# rc2014_16550.net
KiCad netlist of a schematic drawn in EAGLE
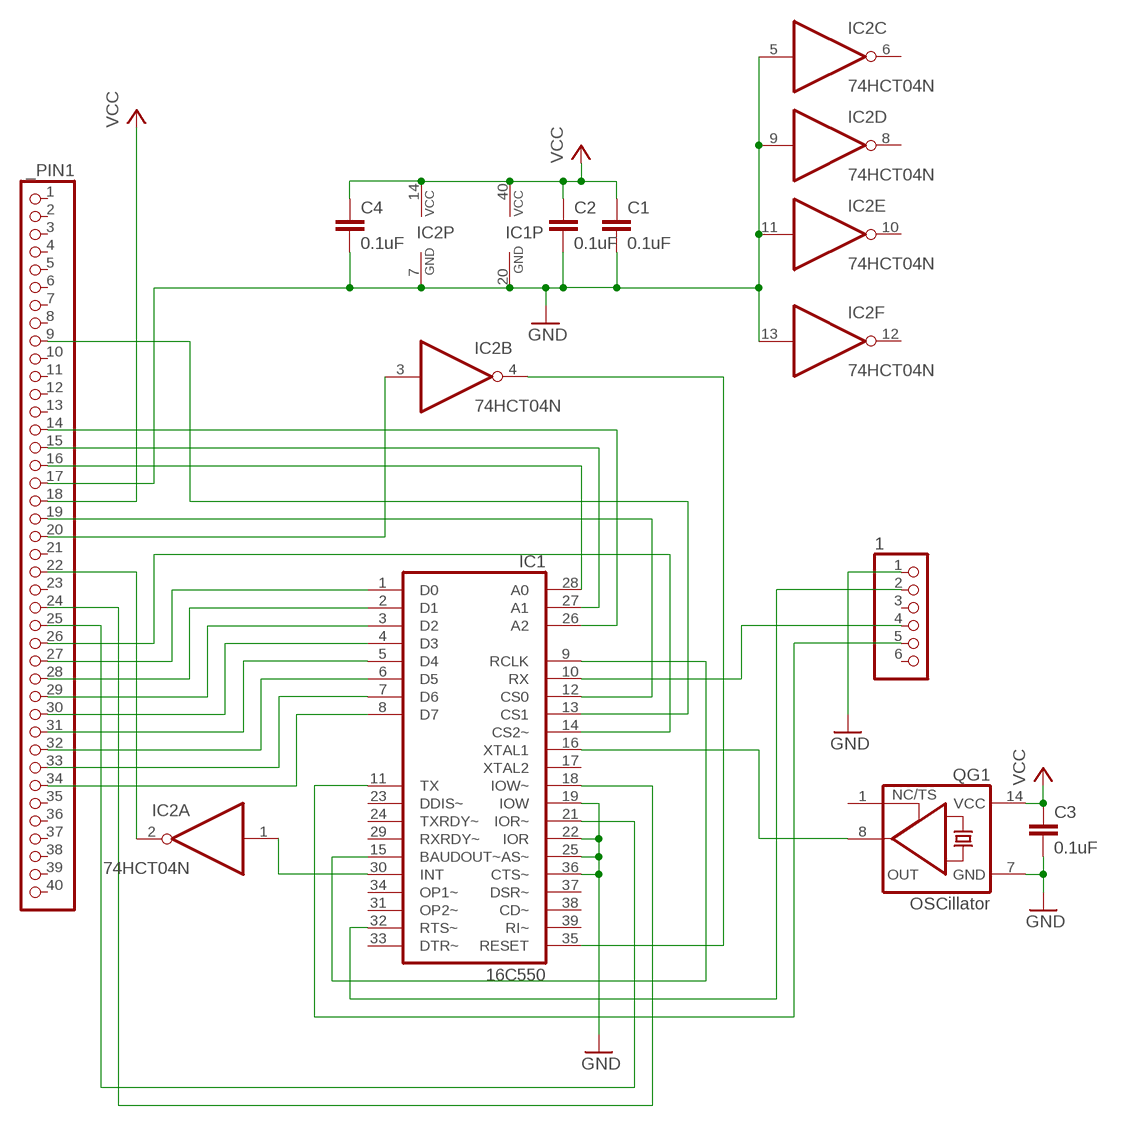
[diagram p0: schematic, sheet 1]

(export (version "E")
  (design (tool "Eeschema 10.0.6"))
  (components
    (comp (ref "1")
      (value "PINHD-1X6")
      (footprint "eagle-import:1X06")
      (libsource (lib "eagle-import") (part "PINHD-1X6"))
    )
    (comp (ref "C1")
      (value "0.1uF")
      (footprint "eagle-import:C050-024X044")
      (libsource (lib "eagle-import") (part "C-EU050-024X044"))
    )
    (comp (ref "C2")
      (value "0.1uF")
      (footprint "eagle-import:C050-024X044")
      (libsource (lib "eagle-import") (part "C-EU050-024X044"))
    )
    (comp (ref "C3")
      (value "0.1uF")
      (footprint "eagle-import:C050-024X044")
      (libsource (lib "eagle-import") (part "C-EU050-024X044"))
    )
    (comp (ref "C4")
      (value "0.1uF")
      (footprint "eagle-import:C050-024X044")
      (libsource (lib "eagle-import") (part "C-EU050-024X044"))
    )
    (comp (ref "IC1")
      (value "16C550")
      (footprint "eagle-import:DIL40")
      (fields (field (name "MPN") "ST16C450CP40"))
      (libsource (lib "eagle-import") (part "XR-16C550P"))
    )
    (comp (ref "IC2")
      (value "74HCT04N")
      (footprint "eagle-import:DIL14")
      (libsource (lib "eagle-import") (part "7404NHCT"))
    )
    (comp (ref "QG1")
      (value "OSCillator")
      (footprint "eagle-import:DIL14S")
      (libsource (lib "eagle-import") (part "XO-14"))
    )
    (comp (ref "_PIN1")
      (value "PINHD-1X40")
      (footprint "eagle-import:1X40")
      (libsource (lib "eagle-import") (part "PINHD-1X40"))
    )
  )
  (nets
    (net (code "1") (name "GND") (class "Default")
      (node (ref "1") (pin "1") (pinfunction "1_1") (pintype "passive"))
      (node (ref "C1") (pin "2") (pinfunction "2_2") (pintype "passive"))
      (node (ref "C2") (pin "2") (pinfunction "2_2") (pintype "passive"))
      (node (ref "C3") (pin "2") (pinfunction "2_2") (pintype "passive"))
      (node (ref "C4") (pin "2") (pinfunction "2_2") (pintype "passive"))
      (node (ref "IC1") (pin "19") (pinfunction "IOW_19") (pintype "input"))
      (node (ref "IC1") (pin "20") (pinfunction "GND_20") (pintype "power_in"))
      (node (ref "IC1") (pin "22") (pinfunction "IOR_22") (pintype "input"))
      (node (ref "IC1") (pin "25") (pinfunction "AS~{}_25") (pintype "input"))
      (node (ref "IC1") (pin "36") (pinfunction "CTS~{}_36") (pintype "input"))
      (node (ref "IC2") (pin "11") (pinfunction "I_11") (pintype "input"))
      (node (ref "IC2") (pin "13") (pinfunction "I_13") (pintype "input"))
      (node (ref "IC2") (pin "5") (pinfunction "I_5") (pintype "input"))
      (node (ref "IC2") (pin "7") (pinfunction "GND_7") (pintype "power_in"))
      (node (ref "IC2") (pin "9") (pinfunction "I_9") (pintype "input"))
      (node (ref "QG1") (pin "7") (pinfunction "GND_7") (pintype "power_in"))
      (node (ref "_PIN1") (pin "17") (pinfunction "17_17") (pintype "passive"))
    )
    (net (code "2") (name "Net-(IC1A-A0)") (class "Default")
      (node (ref "IC1") (pin "28") (pinfunction "A0_28") (pintype "input"))
      (node (ref "_PIN1") (pin "16") (pinfunction "16_16") (pintype "passive"))
    )
    (net (code "3") (name "Net-(IC1A-A1)") (class "Default")
      (node (ref "IC1") (pin "27") (pinfunction "A1_27") (pintype "input"))
      (node (ref "_PIN1") (pin "15") (pinfunction "15_15") (pintype "passive"))
    )
    (net (code "4") (name "Net-(IC1A-A2)") (class "Default")
      (node (ref "IC1") (pin "26") (pinfunction "A2_26") (pintype "input"))
      (node (ref "_PIN1") (pin "14") (pinfunction "14_14") (pintype "passive"))
    )
    (net (code "5") (name "Net-(IC1A-BAUDOUT~{})") (class "Default")
      (node (ref "IC1") (pin "15") (pinfunction "BAUDOUT~{}_15") (pintype "output"))
      (node (ref "IC1") (pin "9") (pinfunction "RCLK_9") (pintype "input"))
    )
    (net (code "6") (name "Net-(IC1A-CS0)") (class "Default")
      (node (ref "IC1") (pin "12") (pinfunction "CS0_12") (pintype "input"))
      (node (ref "_PIN1") (pin "19") (pinfunction "19_19") (pintype "passive"))
    )
    (net (code "7") (name "Net-(IC1A-CS1)") (class "Default")
      (node (ref "IC1") (pin "13") (pinfunction "CS1_13") (pintype "input"))
      (node (ref "_PIN1") (pin "9") (pinfunction "9_9") (pintype "passive"))
    )
    (net (code "8") (name "Net-(IC1A-CS2~{})") (class "Default")
      (node (ref "IC1") (pin "14") (pinfunction "CS2~{}_14") (pintype "input"))
      (node (ref "_PIN1") (pin "26") (pinfunction "26_26") (pintype "passive"))
    )
    (net (code "9") (name "Net-(IC1A-D0)") (class "Default")
      (node (ref "IC1") (pin "1") (pinfunction "D0_1") (pintype "bidirectional"))
      (node (ref "_PIN1") (pin "27") (pinfunction "27_27") (pintype "passive"))
    )
    (net (code "10") (name "Net-(IC1A-D1)") (class "Default")
      (node (ref "IC1") (pin "2") (pinfunction "D1_2") (pintype "bidirectional"))
      (node (ref "_PIN1") (pin "28") (pinfunction "28_28") (pintype "passive"))
    )
    (net (code "11") (name "Net-(IC1A-D2)") (class "Default")
      (node (ref "IC1") (pin "3") (pinfunction "D2_3") (pintype "bidirectional"))
      (node (ref "_PIN1") (pin "29") (pinfunction "29_29") (pintype "passive"))
    )
    (net (code "12") (name "Net-(IC1A-D3)") (class "Default")
      (node (ref "IC1") (pin "4") (pinfunction "D3_4") (pintype "bidirectional"))
      (node (ref "_PIN1") (pin "30") (pinfunction "30_30") (pintype "passive"))
    )
    (net (code "13") (name "Net-(IC1A-D4)") (class "Default")
      (node (ref "IC1") (pin "5") (pinfunction "D4_5") (pintype "bidirectional"))
      (node (ref "_PIN1") (pin "31") (pinfunction "31_31") (pintype "passive"))
    )
    (net (code "14") (name "Net-(IC1A-D5)") (class "Default")
      (node (ref "IC1") (pin "6") (pinfunction "D5_6") (pintype "bidirectional"))
      (node (ref "_PIN1") (pin "32") (pinfunction "32_32") (pintype "passive"))
    )
    (net (code "15") (name "Net-(IC1A-D6)") (class "Default")
      (node (ref "IC1") (pin "7") (pinfunction "D6_7") (pintype "bidirectional"))
      (node (ref "_PIN1") (pin "33") (pinfunction "33_33") (pintype "passive"))
    )
    (net (code "16") (name "Net-(IC1A-D7)") (class "Default")
      (node (ref "IC1") (pin "8") (pinfunction "D7_8") (pintype "bidirectional"))
      (node (ref "_PIN1") (pin "34") (pinfunction "34_34") (pintype "passive"))
    )
    (net (code "17") (name "Net-(IC1A-INT)") (class "Default")
      (node (ref "IC1") (pin "30") (pinfunction "INT_30") (pintype "output"))
      (node (ref "IC2") (pin "1") (pinfunction "I_1") (pintype "input"))
    )
    (net (code "18") (name "Net-(IC1A-IOR~{})") (class "Default")
      (node (ref "IC1") (pin "21") (pinfunction "IOR~{}_21") (pintype "input"))
      (node (ref "_PIN1") (pin "25") (pinfunction "25_25") (pintype "passive"))
    )
    (net (code "19") (name "Net-(IC1A-IOW~{})") (class "Default")
      (node (ref "IC1") (pin "18") (pinfunction "IOW~{}_18") (pintype "input"))
      (node (ref "_PIN1") (pin "24") (pinfunction "24_24") (pintype "passive"))
    )
    (net (code "20") (name "Net-(IC1A-RESET)") (class "Default")
      (node (ref "IC1") (pin "35") (pinfunction "RESET_35") (pintype "input"))
      (node (ref "IC2") (pin "4") (pinfunction "O_4") (pintype "output"))
    )
    (net (code "21") (name "Net-(IC1A-RTS~{})") (class "Default")
      (node (ref "1") (pin "2") (pinfunction "2_2") (pintype "passive"))
      (node (ref "IC1") (pin "32") (pinfunction "RTS~{}_32") (pintype "output"))
    )
    (net (code "22") (name "Net-(IC1A-RX)") (class "Default")
      (node (ref "1") (pin "4") (pinfunction "4_4") (pintype "passive"))
      (node (ref "IC1") (pin "10") (pinfunction "RX_10") (pintype "input"))
    )
    (net (code "23") (name "Net-(IC1A-TX)") (class "Default")
      (node (ref "1") (pin "5") (pinfunction "5_5") (pintype "passive"))
      (node (ref "IC1") (pin "11") (pinfunction "TX_11") (pintype "output"))
    )
    (net (code "24") (name "Net-(IC1A-XTAL1)") (class "Default")
      (node (ref "IC1") (pin "16") (pinfunction "XTAL1_16") (pintype "input"))
      (node (ref "QG1") (pin "8") (pinfunction "OUT_8") (pintype "output"))
    )
    (net (code "25") (name "Net-(IC2A-O)") (class "Default")
      (node (ref "IC2") (pin "2") (pinfunction "O_2") (pintype "output"))
      (node (ref "_PIN1") (pin "22") (pinfunction "22_22") (pintype "passive"))
    )
    (net (code "26") (name "Net-(IC2B-I)") (class "Default")
      (node (ref "IC2") (pin "3") (pinfunction "I_3") (pintype "input"))
      (node (ref "_PIN1") (pin "20") (pinfunction "20_20") (pintype "passive"))
    )
    (net (code "27") (name "VCC") (class "Default")
      (node (ref "C1") (pin "1") (pinfunction "1_1") (pintype "passive"))
      (node (ref "C2") (pin "1") (pinfunction "1_1") (pintype "passive"))
      (node (ref "C3") (pin "1") (pinfunction "1_1") (pintype "passive"))
      (node (ref "C4") (pin "1") (pinfunction "1_1") (pintype "passive"))
      (node (ref "IC1") (pin "40") (pinfunction "VCC_40") (pintype "power_in"))
      (node (ref "IC2") (pin "14") (pinfunction "VCC_14") (pintype "power_in"))
      (node (ref "QG1") (pin "14") (pinfunction "VCC_14") (pintype "power_in"))
      (node (ref "_PIN1") (pin "18") (pinfunction "18_18") (pintype "passive"))
    )
    (net (code "28") (name "unconnected-(1-Pad3)") (class "Default")
      (node (ref "1") (pin "3") (pinfunction "3_3") (pintype "passive"))
    )
    (net (code "29") (name "unconnected-(1-Pad6)") (class "Default")
      (node (ref "1") (pin "6") (pinfunction "6_6") (pintype "passive"))
    )
    (net (code "30") (name "unconnected-(IC1A-CD~{}-Pad38)") (class "Default")
      (node (ref "IC1") (pin "38") (pinfunction "CD~{}_38") (pintype "input"))
    )
    (net (code "31") (name "unconnected-(IC1A-DDIS~{}-Pad23)") (class "Default")
      (node (ref "IC1") (pin "23") (pinfunction "DDIS~{}_23") (pintype "output"))
    )
    (net (code "32") (name "unconnected-(IC1A-DSR~{}-Pad37)") (class "Default")
      (node (ref "IC1") (pin "37") (pinfunction "DSR~{}_37") (pintype "input"))
    )
    (net (code "33") (name "unconnected-(IC1A-DTR~{}-Pad33)") (class "Default")
      (node (ref "IC1") (pin "33") (pinfunction "DTR~{}_33") (pintype "output"))
    )
    (net (code "34") (name "unconnected-(IC1A-OP1~{}-Pad34)") (class "Default")
      (node (ref "IC1") (pin "34") (pinfunction "OP1~{}_34") (pintype "output"))
    )
    (net (code "35") (name "unconnected-(IC1A-OP2~{}-Pad31)") (class "Default")
      (node (ref "IC1") (pin "31") (pinfunction "OP2~{}_31") (pintype "output"))
    )
    (net (code "36") (name "unconnected-(IC1A-RI~{}-Pad39)") (class "Default")
      (node (ref "IC1") (pin "39") (pinfunction "RI~{}_39") (pintype "input"))
    )
    (net (code "37") (name "unconnected-(IC1A-RXRDY~{}-Pad29)") (class "Default")
      (node (ref "IC1") (pin "29") (pinfunction "RXRDY~{}_29") (pintype "output"))
    )
    (net (code "38") (name "unconnected-(IC1A-TXRDY~{}-Pad24)") (class "Default")
      (node (ref "IC1") (pin "24") (pinfunction "TXRDY~{}_24") (pintype "output"))
    )
    (net (code "39") (name "unconnected-(IC1A-XTAL2-Pad17)") (class "Default")
      (node (ref "IC1") (pin "17") (pinfunction "XTAL2_17") (pintype "input"))
    )
    (net (code "40") (name "unconnected-(IC2C-O-Pad6)") (class "Default")
      (node (ref "IC2") (pin "6") (pinfunction "O_6") (pintype "output"))
    )
    (net (code "41") (name "unconnected-(IC2D-O-Pad8)") (class "Default")
      (node (ref "IC2") (pin "8") (pinfunction "O_8") (pintype "output"))
    )
    (net (code "42") (name "unconnected-(IC2E-O-Pad10)") (class "Default")
      (node (ref "IC2") (pin "10") (pinfunction "O_10") (pintype "output"))
    )
    (net (code "43") (name "unconnected-(IC2F-O-Pad12)") (class "Default")
      (node (ref "IC2") (pin "12") (pinfunction "O_12") (pintype "output"))
    )
    (net (code "44") (name "unconnected-(QG1-TS-Pad1)") (class "Default")
      (node (ref "QG1") (pin "1") (pinfunction "TS_1") (pintype "passive"))
    )
    (net (code "45") (name "unconnected-(_PIN1-Pad1)") (class "Default")
      (node (ref "_PIN1") (pin "1") (pinfunction "1_1") (pintype "passive"))
    )
    (net (code "46") (name "unconnected-(_PIN1-Pad2)") (class "Default")
      (node (ref "_PIN1") (pin "2") (pinfunction "2_2") (pintype "passive"))
    )
    (net (code "47") (name "unconnected-(_PIN1-Pad3)") (class "Default")
      (node (ref "_PIN1") (pin "3") (pinfunction "3_3") (pintype "passive"))
    )
    (net (code "48") (name "unconnected-(_PIN1-Pad4)") (class "Default")
      (node (ref "_PIN1") (pin "4") (pinfunction "4_4") (pintype "passive"))
    )
    (net (code "49") (name "unconnected-(_PIN1-Pad5)") (class "Default")
      (node (ref "_PIN1") (pin "5") (pinfunction "5_5") (pintype "passive"))
    )
    (net (code "50") (name "unconnected-(_PIN1-Pad6)") (class "Default")
      (node (ref "_PIN1") (pin "6") (pinfunction "6_6") (pintype "passive"))
    )
    (net (code "51") (name "unconnected-(_PIN1-Pad7)") (class "Default")
      (node (ref "_PIN1") (pin "7") (pinfunction "7_7") (pintype "passive"))
    )
    (net (code "52") (name "unconnected-(_PIN1-Pad8)") (class "Default")
      (node (ref "_PIN1") (pin "8") (pinfunction "8_8") (pintype "passive"))
    )
    (net (code "53") (name "unconnected-(_PIN1-Pad10)") (class "Default")
      (node (ref "_PIN1") (pin "10") (pinfunction "10_10") (pintype "passive"))
    )
    (net (code "54") (name "unconnected-(_PIN1-Pad11)") (class "Default")
      (node (ref "_PIN1") (pin "11") (pinfunction "11_11") (pintype "passive"))
    )
    (net (code "55") (name "unconnected-(_PIN1-Pad12)") (class "Default")
      (node (ref "_PIN1") (pin "12") (pinfunction "12_12") (pintype "passive"))
    )
    (net (code "56") (name "unconnected-(_PIN1-Pad13)") (class "Default")
      (node (ref "_PIN1") (pin "13") (pinfunction "13_13") (pintype "passive"))
    )
    (net (code "57") (name "unconnected-(_PIN1-Pad21)") (class "Default")
      (node (ref "_PIN1") (pin "21") (pinfunction "21_21") (pintype "passive"))
    )
    (net (code "58") (name "unconnected-(_PIN1-Pad23)") (class "Default")
      (node (ref "_PIN1") (pin "23") (pinfunction "23_23") (pintype "passive"))
    )
    (net (code "59") (name "unconnected-(_PIN1-Pad35)") (class "Default")
      (node (ref "_PIN1") (pin "35") (pinfunction "35_35") (pintype "passive"))
    )
    (net (code "60") (name "unconnected-(_PIN1-Pad36)") (class "Default")
      (node (ref "_PIN1") (pin "36") (pinfunction "36_36") (pintype "passive"))
    )
    (net (code "61") (name "unconnected-(_PIN1-Pad37)") (class "Default")
      (node (ref "_PIN1") (pin "37") (pinfunction "37_37") (pintype "passive"))
    )
    (net (code "62") (name "unconnected-(_PIN1-Pad38)") (class "Default")
      (node (ref "_PIN1") (pin "38") (pinfunction "38_38") (pintype "passive"))
    )
    (net (code "63") (name "unconnected-(_PIN1-Pad39)") (class "Default")
      (node (ref "_PIN1") (pin "39") (pinfunction "39_39") (pintype "passive"))
    )
    (net (code "64") (name "unconnected-(_PIN1-Pad40)") (class "Default")
      (node (ref "_PIN1") (pin "40") (pinfunction "40_40") (pintype "passive"))
    )
  )
)
